# LED_Bargraph.net
KiCad netlist of a schematic drawn in Altium Designer
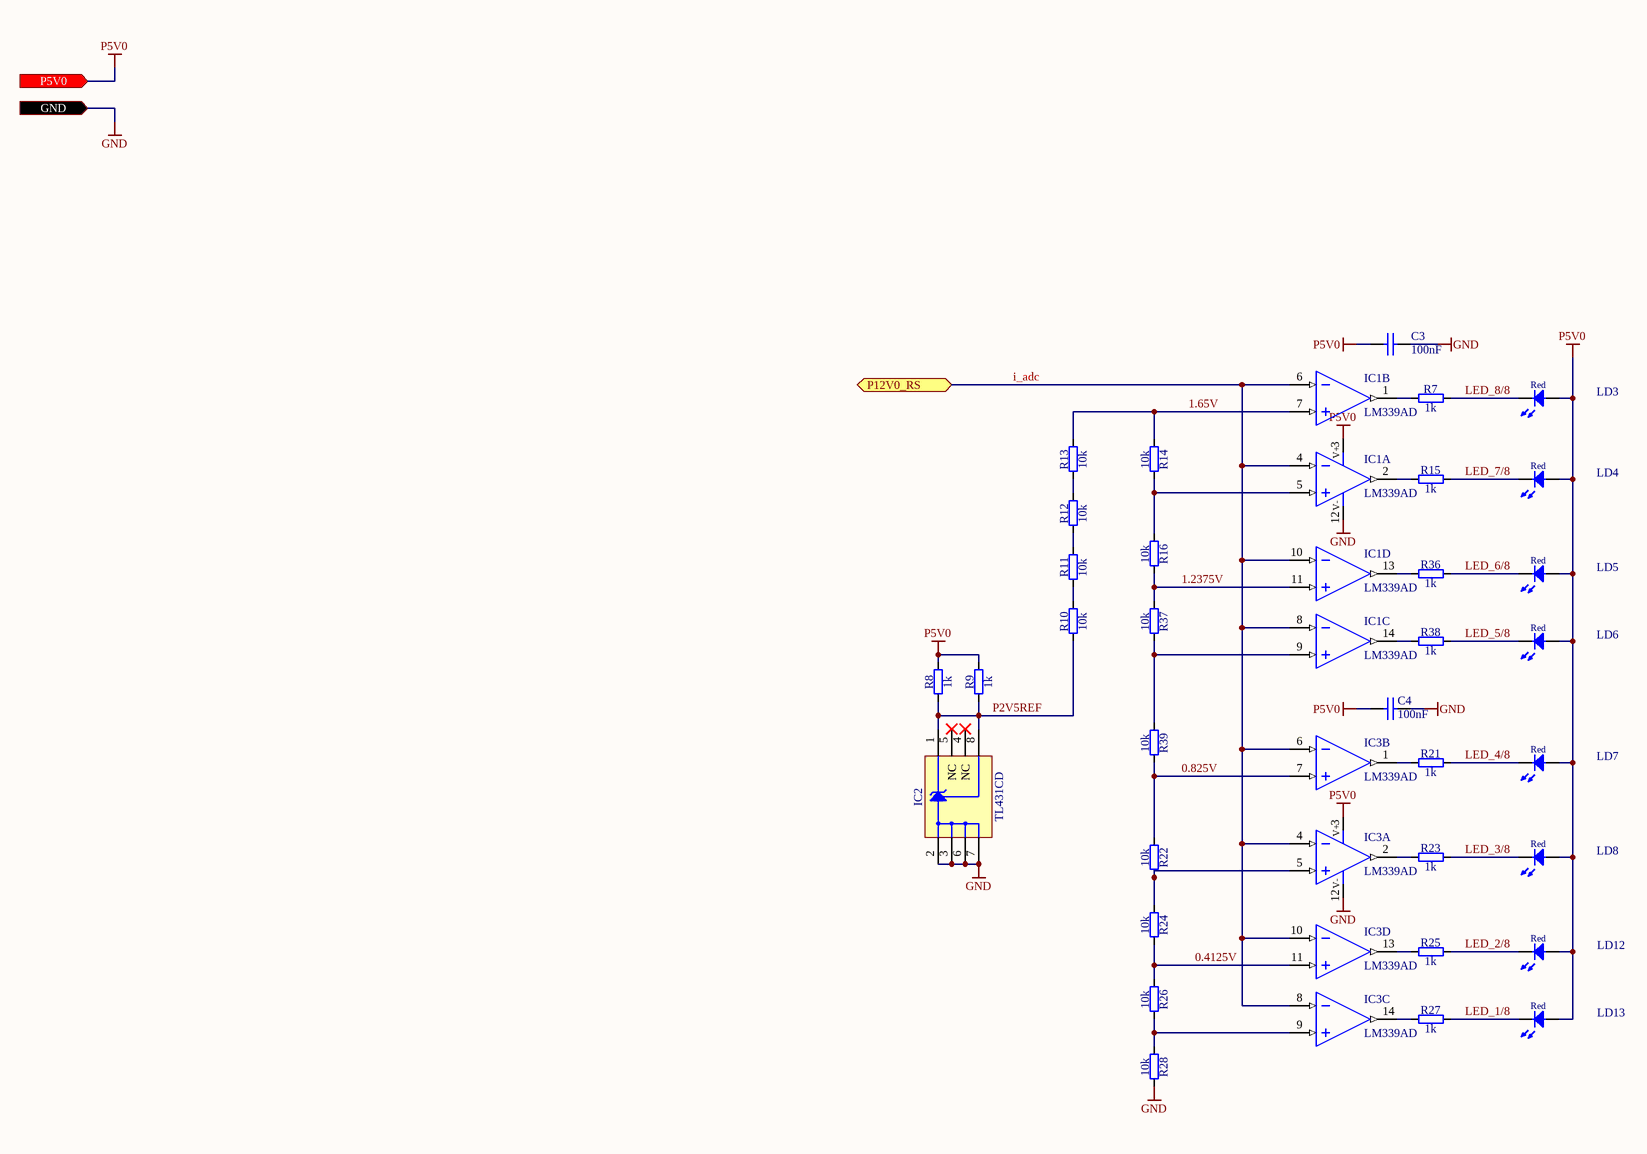
[diagram p0: LED_Bargraph.SchDoc]

(export (version "E")
  (design (tool "Eeschema 10.0.6"))
  (components
    (comp (ref "C3")
      (value "100nF")
      (footprint "CAPC1608X87N")
      (description "Non-polarised capacitor")
      (fields
        (field (name "PART NUMBER") "CC0603_100NF_50V_10%_X5R")
        (field (name "VOLTAGE") "50V")
        (field (name "AUTHOR") "CERN DEM MR")
      )
      (libsource (lib "Capacitors") (part "Capacitor - non polarized"))
    )
    (comp (ref "C4")
      (value "100nF")
      (footprint "CAPC1608X87N")
      (description "Non-polarised capacitor")
      (fields
        (field (name "PART NUMBER") "CC0603_100NF_50V_10%_X5R")
        (field (name "VOLTAGE") "50V")
        (field (name "AUTHOR") "CERN DEM MR")
      )
      (libsource (lib "Capacitors") (part "Capacitor - non polarized"))
    )
    (comp (ref "IC1")
      (value "LM339AD")
      (footprint "SOIC127P600X175-14N")
      (description "Quad Operational Amplifier")
      (fields (field (name "MANUFACTURER") "TEXAS INSTRUMENTS") (field (name "AUTHOR") "CERN DEM JLC"))
      (libsource (lib "EDA-04213-V3-0_project") (part "LM339AD"))
    )
    (comp (ref "IC2")
      (value "TL431CD")
      (footprint "SOIC127P600X175-8N")
      (description "Precision Programmable Reference")
      (fields (field (name "MANUFACTURER") "TEXAS INSTRUMENTS") (field (name "AUTHOR") "CERN DEM JLC"))
      (libsource (lib "ICs And Semiconductors") (part "TL431xD"))
    )
    (comp (ref "IC3")
      (value "LM339AD")
      (footprint "SOIC127P600X175-14N")
      (description "Quad Operational Amplifier")
      (fields (field (name "MANUFACTURER") "TEXAS INSTRUMENTS") (field (name "AUTHOR") "CERN DEM JLC"))
      (libsource (lib "EDA-04213-V3-0_project") (part "LM339AD"))
    )
    (comp (ref "LD3")
      (value "Red")
      (footprint "LED_AVAGO_HSMC-C120")
      (description "LED Red 1C 2A")
      (fields
        (field (name "PART NUMBER") "LED_AVAGO_HSMC-C120")
        (field (name "MANUFACTURER") "AVAGO TECHNOLOGIES")
        (field (name "AUTHOR") "CERN DEM JMW")
      )
      (libsource (lib "ICs And Semiconductors") (part "LED Red 1C 2A"))
    )
    (comp (ref "LD4")
      (value "Red")
      (footprint "LED_AVAGO_HSMC-C120")
      (description "LED Red 1C 2A")
      (fields
        (field (name "PART NUMBER") "LED_AVAGO_HSMC-C120")
        (field (name "MANUFACTURER") "AVAGO TECHNOLOGIES")
        (field (name "AUTHOR") "CERN DEM JMW")
      )
      (libsource (lib "ICs And Semiconductors") (part "LED Red 1C 2A"))
    )
    (comp (ref "LD5")
      (value "Red")
      (footprint "LED_AVAGO_HSMC-C120")
      (description "LED Red 1C 2A")
      (fields
        (field (name "PART NUMBER") "LED_AVAGO_HSMC-C120")
        (field (name "MANUFACTURER") "AVAGO TECHNOLOGIES")
        (field (name "AUTHOR") "CERN DEM JMW")
      )
      (libsource (lib "ICs And Semiconductors") (part "LED Red 1C 2A"))
    )
    (comp (ref "LD6")
      (value "Red")
      (footprint "LED_AVAGO_HSMC-C120")
      (description "LED Red 1C 2A")
      (fields
        (field (name "PART NUMBER") "LED_AVAGO_HSMC-C120")
        (field (name "MANUFACTURER") "AVAGO TECHNOLOGIES")
        (field (name "AUTHOR") "CERN DEM JMW")
      )
      (libsource (lib "ICs And Semiconductors") (part "LED Red 1C 2A"))
    )
    (comp (ref "LD7")
      (value "Red")
      (footprint "LED_AVAGO_HSMC-C120")
      (description "LED Red 1C 2A")
      (fields
        (field (name "PART NUMBER") "LED_AVAGO_HSMC-C120")
        (field (name "MANUFACTURER") "AVAGO TECHNOLOGIES")
        (field (name "AUTHOR") "CERN DEM JMW")
      )
      (libsource (lib "ICs And Semiconductors") (part "LED Red 1C 2A"))
    )
    (comp (ref "LD8")
      (value "Red")
      (footprint "LED_AVAGO_HSMC-C120")
      (description "LED Red 1C 2A")
      (fields
        (field (name "PART NUMBER") "LED_AVAGO_HSMC-C120")
        (field (name "MANUFACTURER") "AVAGO TECHNOLOGIES")
        (field (name "AUTHOR") "CERN DEM JMW")
      )
      (libsource (lib "ICs And Semiconductors") (part "LED Red 1C 2A"))
    )
    (comp (ref "LD12")
      (value "Red")
      (footprint "LED_AVAGO_HSMC-C120")
      (description "LED Red 1C 2A")
      (fields
        (field (name "PART NUMBER") "LED_AVAGO_HSMC-C120")
        (field (name "MANUFACTURER") "AVAGO TECHNOLOGIES")
        (field (name "AUTHOR") "CERN DEM JMW")
      )
      (libsource (lib "ICs And Semiconductors") (part "LED Red 1C 2A"))
    )
    (comp (ref "LD13")
      (value "Red")
      (footprint "LED_AVAGO_HSMC-C120")
      (description "LED Red 1C 2A")
      (fields
        (field (name "PART NUMBER") "LED_AVAGO_HSMC-C120")
        (field (name "MANUFACTURER") "AVAGO TECHNOLOGIES")
        (field (name "AUTHOR") "CERN DEM JMW")
      )
      (libsource (lib "ICs And Semiconductors") (part "LED Red 1C 2A"))
    )
    (comp (ref "R7")
      (value "1k")
      (footprint "RESC1608X55N")
      (description "Resistor - 1%")
      (fields
        (field (name "PART NUMBER") "R0603_1K_1%_0.1W_100PPM")
        (field (name "POWER") "0.1W")
        (field (name "AUTHOR") "CERN DEM JLC")
      )
      (libsource (lib "Resistors") (part "Resistor - 1%"))
    )
    (comp (ref "R8")
      (value "1k")
      (footprint "RESC1608X55N")
      (description "Resistor - 1%")
      (fields
        (field (name "PART NUMBER") "R0603_1K_1%_0.1W_100PPM")
        (field (name "POWER") "0.1W")
        (field (name "AUTHOR") "CERN DEM JLC")
      )
      (libsource (lib "Resistors") (part "Resistor - 1%"))
    )
    (comp (ref "R9")
      (value "1k")
      (footprint "RESC1608X55N")
      (description "Resistor - 1%")
      (fields
        (field (name "PART NUMBER") "R0603_1K_1%_0.1W_100PPM")
        (field (name "POWER") "0.1W")
        (field (name "AUTHOR") "CERN DEM JLC")
      )
      (libsource (lib "Resistors") (part "Resistor - 1%"))
    )
    (comp (ref "R10")
      (value "10k")
      (footprint "RESC1608X55N")
      (description "Resistor - 1%")
      (fields
        (field (name "PART NUMBER") "R0603_10K_1%_0.1W_100PPM")
        (field (name "POWER") "0.1W")
        (field (name "AUTHOR") "CERN DEM JLC")
      )
      (libsource (lib "Resistors") (part "Resistor - 1%"))
    )
    (comp (ref "R11")
      (value "10k")
      (footprint "RESC1608X55N")
      (description "Resistor - 1%")
      (fields
        (field (name "PART NUMBER") "R0603_10K_1%_0.1W_100PPM")
        (field (name "POWER") "0.1W")
        (field (name "AUTHOR") "CERN DEM JLC")
      )
      (libsource (lib "Resistors") (part "Resistor - 1%"))
    )
    (comp (ref "R12")
      (value "10k")
      (footprint "RESC1608X55N")
      (description "Resistor - 1%")
      (fields
        (field (name "PART NUMBER") "R0603_10K_1%_0.1W_100PPM")
        (field (name "POWER") "0.1W")
        (field (name "AUTHOR") "CERN DEM JLC")
      )
      (libsource (lib "Resistors") (part "Resistor - 1%"))
    )
    (comp (ref "R13")
      (value "10k")
      (footprint "RESC1608X55N")
      (description "Resistor - 1%")
      (fields
        (field (name "PART NUMBER") "R0603_10K_1%_0.1W_100PPM")
        (field (name "POWER") "0.1W")
        (field (name "AUTHOR") "CERN DEM JLC")
      )
      (libsource (lib "Resistors") (part "Resistor - 1%"))
    )
    (comp (ref "R14")
      (value "10k")
      (footprint "RESC1608X55N")
      (description "Resistor - 1%")
      (fields
        (field (name "PART NUMBER") "R0603_10K_1%_0.1W_100PPM")
        (field (name "POWER") "0.1W")
        (field (name "AUTHOR") "CERN DEM JLC")
      )
      (libsource (lib "Resistors") (part "Resistor - 1%"))
    )
    (comp (ref "R15")
      (value "1k")
      (footprint "RESC1608X55N")
      (description "Resistor - 1%")
      (fields
        (field (name "PART NUMBER") "R0603_1K_1%_0.1W_100PPM")
        (field (name "POWER") "0.1W")
        (field (name "AUTHOR") "CERN DEM JLC")
      )
      (libsource (lib "Resistors") (part "Resistor - 1%"))
    )
    (comp (ref "R16")
      (value "10k")
      (footprint "RESC1608X55N")
      (description "Resistor - 1%")
      (fields
        (field (name "PART NUMBER") "R0603_10K_1%_0.1W_100PPM")
        (field (name "POWER") "0.1W")
        (field (name "AUTHOR") "CERN DEM JLC")
      )
      (libsource (lib "Resistors") (part "Resistor - 1%"))
    )
    (comp (ref "R21")
      (value "1k")
      (footprint "RESC1608X55N")
      (description "Resistor - 1%")
      (fields
        (field (name "PART NUMBER") "R0603_1K_1%_0.1W_100PPM")
        (field (name "POWER") "0.1W")
        (field (name "AUTHOR") "CERN DEM JLC")
      )
      (libsource (lib "Resistors") (part "Resistor - 1%"))
    )
    (comp (ref "R22")
      (value "10k")
      (footprint "RESC1608X55N")
      (description "Resistor - 1%")
      (fields
        (field (name "PART NUMBER") "R0603_10K_1%_0.1W_100PPM")
        (field (name "POWER") "0.1W")
        (field (name "AUTHOR") "CERN DEM JLC")
      )
      (libsource (lib "Resistors") (part "Resistor - 1%"))
    )
    (comp (ref "R23")
      (value "1k")
      (footprint "RESC1608X55N")
      (description "Resistor - 1%")
      (fields
        (field (name "PART NUMBER") "R0603_1K_1%_0.1W_100PPM")
        (field (name "POWER") "0.1W")
        (field (name "AUTHOR") "CERN DEM JLC")
      )
      (libsource (lib "Resistors") (part "Resistor - 1%"))
    )
    (comp (ref "R24")
      (value "10k")
      (footprint "RESC1608X55N")
      (description "Resistor - 1%")
      (fields
        (field (name "PART NUMBER") "R0603_10K_1%_0.1W_100PPM")
        (field (name "POWER") "0.1W")
        (field (name "AUTHOR") "CERN DEM JLC")
      )
      (libsource (lib "Resistors") (part "Resistor - 1%"))
    )
    (comp (ref "R25")
      (value "1k")
      (footprint "RESC1608X55N")
      (description "Resistor - 1%")
      (fields
        (field (name "PART NUMBER") "R0603_1K_1%_0.1W_100PPM")
        (field (name "POWER") "0.1W")
        (field (name "AUTHOR") "CERN DEM JLC")
      )
      (libsource (lib "Resistors") (part "Resistor - 1%"))
    )
    (comp (ref "R26")
      (value "10k")
      (footprint "RESC1608X55N")
      (description "Resistor - 1%")
      (fields
        (field (name "PART NUMBER") "R0603_10K_1%_0.1W_100PPM")
        (field (name "POWER") "0.1W")
        (field (name "AUTHOR") "CERN DEM JLC")
      )
      (libsource (lib "Resistors") (part "Resistor - 1%"))
    )
    (comp (ref "R27")
      (value "1k")
      (footprint "RESC1608X55N")
      (description "Resistor - 1%")
      (fields
        (field (name "PART NUMBER") "R0603_1K_1%_0.1W_100PPM")
        (field (name "POWER") "0.1W")
        (field (name "AUTHOR") "CERN DEM JLC")
      )
      (libsource (lib "Resistors") (part "Resistor - 1%"))
    )
    (comp (ref "R28")
      (value "10k")
      (footprint "RESC1608X55N")
      (description "Resistor - 1%")
      (fields
        (field (name "PART NUMBER") "R0603_10K_1%_0.1W_100PPM")
        (field (name "POWER") "0.1W")
        (field (name "AUTHOR") "CERN DEM JLC")
      )
      (libsource (lib "Resistors") (part "Resistor - 1%"))
    )
    (comp (ref "R36")
      (value "1k")
      (footprint "RESC1608X55N")
      (description "Resistor - 1%")
      (fields
        (field (name "PART NUMBER") "R0603_1K_1%_0.1W_100PPM")
        (field (name "POWER") "0.1W")
        (field (name "AUTHOR") "CERN DEM JLC")
      )
      (libsource (lib "Resistors") (part "Resistor - 1%"))
    )
    (comp (ref "R37")
      (value "10k")
      (footprint "RESC1608X55N")
      (description "Resistor - 1%")
      (fields
        (field (name "PART NUMBER") "R0603_10K_1%_0.1W_100PPM")
        (field (name "POWER") "0.1W")
        (field (name "AUTHOR") "CERN DEM JLC")
      )
      (libsource (lib "Resistors") (part "Resistor - 1%"))
    )
    (comp (ref "R38")
      (value "1k")
      (footprint "RESC1608X55N")
      (description "Resistor - 1%")
      (fields
        (field (name "PART NUMBER") "R0603_1K_1%_0.1W_100PPM")
        (field (name "POWER") "0.1W")
        (field (name "AUTHOR") "CERN DEM JLC")
      )
      (libsource (lib "Resistors") (part "Resistor - 1%"))
    )
    (comp (ref "R39")
      (value "10k")
      (footprint "RESC1608X55N")
      (description "Resistor - 1%")
      (fields
        (field (name "PART NUMBER") "R0603_10K_1%_0.1W_100PPM")
        (field (name "POWER") "0.1W")
        (field (name "AUTHOR") "CERN DEM JLC")
      )
      (libsource (lib "Resistors") (part "Resistor - 1%"))
    )
  )
  (nets
    (net (code "1") (name "/0.825V") (class "Default")
      (node (ref "IC3") (pin "7") (pinfunction "IN+_7") (pintype "input"))
      (node (ref "R22") (pin "1") (pinfunction "1_1") (pintype "passive"))
      (node (ref "R39") (pin "2") (pinfunction "2_2") (pintype "passive"))
    )
    (net (code "2") (name "/0.4125V") (class "Default")
      (node (ref "IC3") (pin "11") (pinfunction "IN+_11") (pintype "input"))
      (node (ref "R24") (pin "2") (pinfunction "2_2") (pintype "passive"))
      (node (ref "R26") (pin "1") (pinfunction "1_1") (pintype "passive"))
    )
    (net (code "3") (name "/1.65V") (class "Default")
      (node (ref "IC1") (pin "7") (pinfunction "IN+_7") (pintype "input"))
      (node (ref "R13") (pin "2") (pinfunction "2_2") (pintype "passive"))
      (node (ref "R14") (pin "1") (pinfunction "1_1") (pintype "passive"))
    )
    (net (code "4") (name "/1.2375V") (class "Default")
      (node (ref "IC1") (pin "11") (pinfunction "IN+_11") (pintype "input"))
      (node (ref "R16") (pin "2") (pinfunction "2_2") (pintype "passive"))
      (node (ref "R37") (pin "1") (pinfunction "1_1") (pintype "passive"))
    )
    (net (code "5") (name "/LED_1{slash}8") (class "Default")
      (node (ref "LD13") (pin "1") (pinfunction "C_1") (pintype "passive"))
      (node (ref "R27") (pin "2") (pinfunction "2_2") (pintype "passive"))
    )
    (net (code "6") (name "/LED_2{slash}8") (class "Default")
      (node (ref "LD12") (pin "1") (pinfunction "C_1") (pintype "passive"))
      (node (ref "R25") (pin "2") (pinfunction "2_2") (pintype "passive"))
    )
    (net (code "7") (name "/LED_3{slash}8") (class "Default")
      (node (ref "LD8") (pin "1") (pinfunction "C_1") (pintype "passive"))
      (node (ref "R23") (pin "2") (pinfunction "2_2") (pintype "passive"))
    )
    (net (code "8") (name "/LED_4{slash}8") (class "Default")
      (node (ref "LD7") (pin "1") (pinfunction "C_1") (pintype "passive"))
      (node (ref "R21") (pin "2") (pinfunction "2_2") (pintype "passive"))
    )
    (net (code "9") (name "/LED_5{slash}8") (class "Default")
      (node (ref "LD6") (pin "1") (pinfunction "C_1") (pintype "passive"))
      (node (ref "R38") (pin "2") (pinfunction "2_2") (pintype "passive"))
    )
    (net (code "10") (name "/LED_6{slash}8") (class "Default")
      (node (ref "LD5") (pin "1") (pinfunction "C_1") (pintype "passive"))
      (node (ref "R36") (pin "2") (pinfunction "2_2") (pintype "passive"))
    )
    (net (code "11") (name "/LED_7{slash}8") (class "Default")
      (node (ref "LD4") (pin "1") (pinfunction "C_1") (pintype "passive"))
      (node (ref "R15") (pin "2") (pinfunction "2_2") (pintype "passive"))
    )
    (net (code "12") (name "/LED_8{slash}8") (class "Default")
      (node (ref "LD3") (pin "1") (pinfunction "C_1") (pintype "passive"))
      (node (ref "R7") (pin "2") (pinfunction "2_2") (pintype "passive"))
    )
    (net (code "13") (name "/P2V5REF") (class "Default")
      (node (ref "IC2") (pin "1") (pinfunction "C_1") (pintype "passive"))
      (node (ref "IC2") (pin "8") (pinfunction "REF_8") (pintype "passive"))
      (node (ref "R10") (pin "1") (pinfunction "1_1") (pintype "passive"))
      (node (ref "R8") (pin "1") (pinfunction "1_1") (pintype "passive"))
      (node (ref "R9") (pin "1") (pinfunction "1_1") (pintype "passive"))
    )
    (net (code "14") (name "/i_adc") (class "Default")
      (node (ref "IC1") (pin "10") (pinfunction "IN-_10") (pintype "input"))
      (node (ref "IC1") (pin "4") (pinfunction "IN-_4") (pintype "input"))
      (node (ref "IC1") (pin "6") (pinfunction "IN-_6") (pintype "input"))
      (node (ref "IC1") (pin "8") (pinfunction "IN-_8") (pintype "input"))
      (node (ref "IC3") (pin "10") (pinfunction "IN-_10") (pintype "input"))
      (node (ref "IC3") (pin "4") (pinfunction "IN-_4") (pintype "input"))
      (node (ref "IC3") (pin "6") (pinfunction "IN-_6") (pintype "input"))
      (node (ref "IC3") (pin "8") (pinfunction "IN-_8") (pintype "input"))
    )
    (net (code "15") (name "GND") (class "Default")
      (node (ref "C3") (pin "2") (pinfunction "2_2") (pintype "passive"))
      (node (ref "C4") (pin "2") (pinfunction "2_2") (pintype "passive"))
      (node (ref "IC1") (pin "12") (pinfunction "V-_12") (pintype "passive"))
      (node (ref "IC2") (pin "2") (pinfunction "A_2") (pintype "passive"))
      (node (ref "IC2") (pin "3") (pinfunction "A_3") (pintype "passive"))
      (node (ref "IC2") (pin "6") (pinfunction "A_6") (pintype "passive"))
      (node (ref "IC2") (pin "7") (pinfunction "A_7") (pintype "passive"))
      (node (ref "IC3") (pin "12") (pinfunction "V-_12") (pintype "passive"))
      (node (ref "R28") (pin "2") (pinfunction "2_2") (pintype "passive"))
    )
    (net (code "16") (name "Net-(IC1A-IN+)") (class "Default")
      (node (ref "IC1") (pin "5") (pinfunction "IN+_5") (pintype "input"))
      (node (ref "R14") (pin "2") (pinfunction "2_2") (pintype "passive"))
      (node (ref "R16") (pin "1") (pinfunction "1_1") (pintype "passive"))
    )
    (net (code "17") (name "Net-(IC1A-OUT)") (class "Default")
      (node (ref "IC1") (pin "2") (pinfunction "OUT_2") (pintype "output"))
      (node (ref "R15") (pin "1") (pinfunction "1_1") (pintype "passive"))
    )
    (net (code "18") (name "Net-(IC1B-OUT)") (class "Default")
      (node (ref "IC1") (pin "1") (pinfunction "OUT_1") (pintype "output"))
      (node (ref "R7") (pin "1") (pinfunction "1_1") (pintype "passive"))
    )
    (net (code "19") (name "Net-(IC1C-IN+)") (class "Default")
      (node (ref "IC1") (pin "9") (pinfunction "IN+_9") (pintype "input"))
      (node (ref "R37") (pin "2") (pinfunction "2_2") (pintype "passive"))
      (node (ref "R39") (pin "1") (pinfunction "1_1") (pintype "passive"))
    )
    (net (code "20") (name "Net-(IC1C-OUT)") (class "Default")
      (node (ref "IC1") (pin "14") (pinfunction "OUT_14") (pintype "output"))
      (node (ref "R38") (pin "1") (pinfunction "1_1") (pintype "passive"))
    )
    (net (code "21") (name "Net-(IC1D-OUT)") (class "Default")
      (node (ref "IC1") (pin "13") (pinfunction "OUT_13") (pintype "output"))
      (node (ref "R36") (pin "1") (pinfunction "1_1") (pintype "passive"))
    )
    (net (code "22") (name "Net-(IC3A-IN+)") (class "Default")
      (node (ref "IC3") (pin "5") (pinfunction "IN+_5") (pintype "input"))
      (node (ref "R22") (pin "2") (pinfunction "2_2") (pintype "passive"))
      (node (ref "R24") (pin "1") (pinfunction "1_1") (pintype "passive"))
    )
    (net (code "23") (name "Net-(IC3A-OUT)") (class "Default")
      (node (ref "IC3") (pin "2") (pinfunction "OUT_2") (pintype "output"))
      (node (ref "R23") (pin "1") (pinfunction "1_1") (pintype "passive"))
    )
    (net (code "24") (name "Net-(IC3B-OUT)") (class "Default")
      (node (ref "IC3") (pin "1") (pinfunction "OUT_1") (pintype "output"))
      (node (ref "R21") (pin "1") (pinfunction "1_1") (pintype "passive"))
    )
    (net (code "25") (name "Net-(IC3C-IN+)") (class "Default")
      (node (ref "IC3") (pin "9") (pinfunction "IN+_9") (pintype "input"))
      (node (ref "R26") (pin "2") (pinfunction "2_2") (pintype "passive"))
      (node (ref "R28") (pin "1") (pinfunction "1_1") (pintype "passive"))
    )
    (net (code "26") (name "Net-(IC3C-OUT)") (class "Default")
      (node (ref "IC3") (pin "14") (pinfunction "OUT_14") (pintype "output"))
      (node (ref "R27") (pin "1") (pinfunction "1_1") (pintype "passive"))
    )
    (net (code "27") (name "Net-(IC3D-OUT)") (class "Default")
      (node (ref "IC3") (pin "13") (pinfunction "OUT_13") (pintype "output"))
      (node (ref "R25") (pin "1") (pinfunction "1_1") (pintype "passive"))
    )
    (net (code "28") (name "Net-(R10-Pad2)") (class "Default")
      (node (ref "R10") (pin "2") (pinfunction "2_2") (pintype "passive"))
      (node (ref "R11") (pin "1") (pinfunction "1_1") (pintype "passive"))
    )
    (net (code "29") (name "Net-(R11-Pad2)") (class "Default")
      (node (ref "R11") (pin "2") (pinfunction "2_2") (pintype "passive"))
      (node (ref "R12") (pin "1") (pinfunction "1_1") (pintype "passive"))
    )
    (net (code "30") (name "Net-(R12-Pad2)") (class "Default")
      (node (ref "R12") (pin "2") (pinfunction "2_2") (pintype "passive"))
      (node (ref "R13") (pin "1") (pinfunction "1_1") (pintype "passive"))
    )
    (net (code "31") (name "P5V0") (class "Default")
      (node (ref "C3") (pin "1") (pinfunction "1_1") (pintype "passive"))
      (node (ref "C4") (pin "1") (pinfunction "1_1") (pintype "passive"))
      (node (ref "IC1") (pin "3") (pinfunction "V+_3") (pintype "passive"))
      (node (ref "IC3") (pin "3") (pinfunction "V+_3") (pintype "passive"))
      (node (ref "LD12") (pin "2") (pinfunction "A_2") (pintype "passive"))
      (node (ref "LD13") (pin "2") (pinfunction "A_2") (pintype "passive"))
      (node (ref "LD3") (pin "2") (pinfunction "A_2") (pintype "passive"))
      (node (ref "LD4") (pin "2") (pinfunction "A_2") (pintype "passive"))
      (node (ref "LD5") (pin "2") (pinfunction "A_2") (pintype "passive"))
      (node (ref "LD6") (pin "2") (pinfunction "A_2") (pintype "passive"))
      (node (ref "LD7") (pin "2") (pinfunction "A_2") (pintype "passive"))
      (node (ref "LD8") (pin "2") (pinfunction "A_2") (pintype "passive"))
      (node (ref "R8") (pin "2") (pinfunction "2_2") (pintype "passive"))
      (node (ref "R9") (pin "2") (pinfunction "2_2") (pintype "passive"))
    )
    (net (code "32") (name "unconnected-(IC2-NC-Pad4)") (class "Default")
      (node (ref "IC2") (pin "4") (pinfunction "NC_4") (pintype "passive+no_connect"))
    )
    (net (code "33") (name "unconnected-(IC2-NC-Pad5)") (class "Default")
      (node (ref "IC2") (pin "5") (pinfunction "NC_5") (pintype "passive+no_connect"))
    )
  )
)
